# Supply_HV_ISOL.net
KiCad netlist of a schematic drawn in Altium Designer
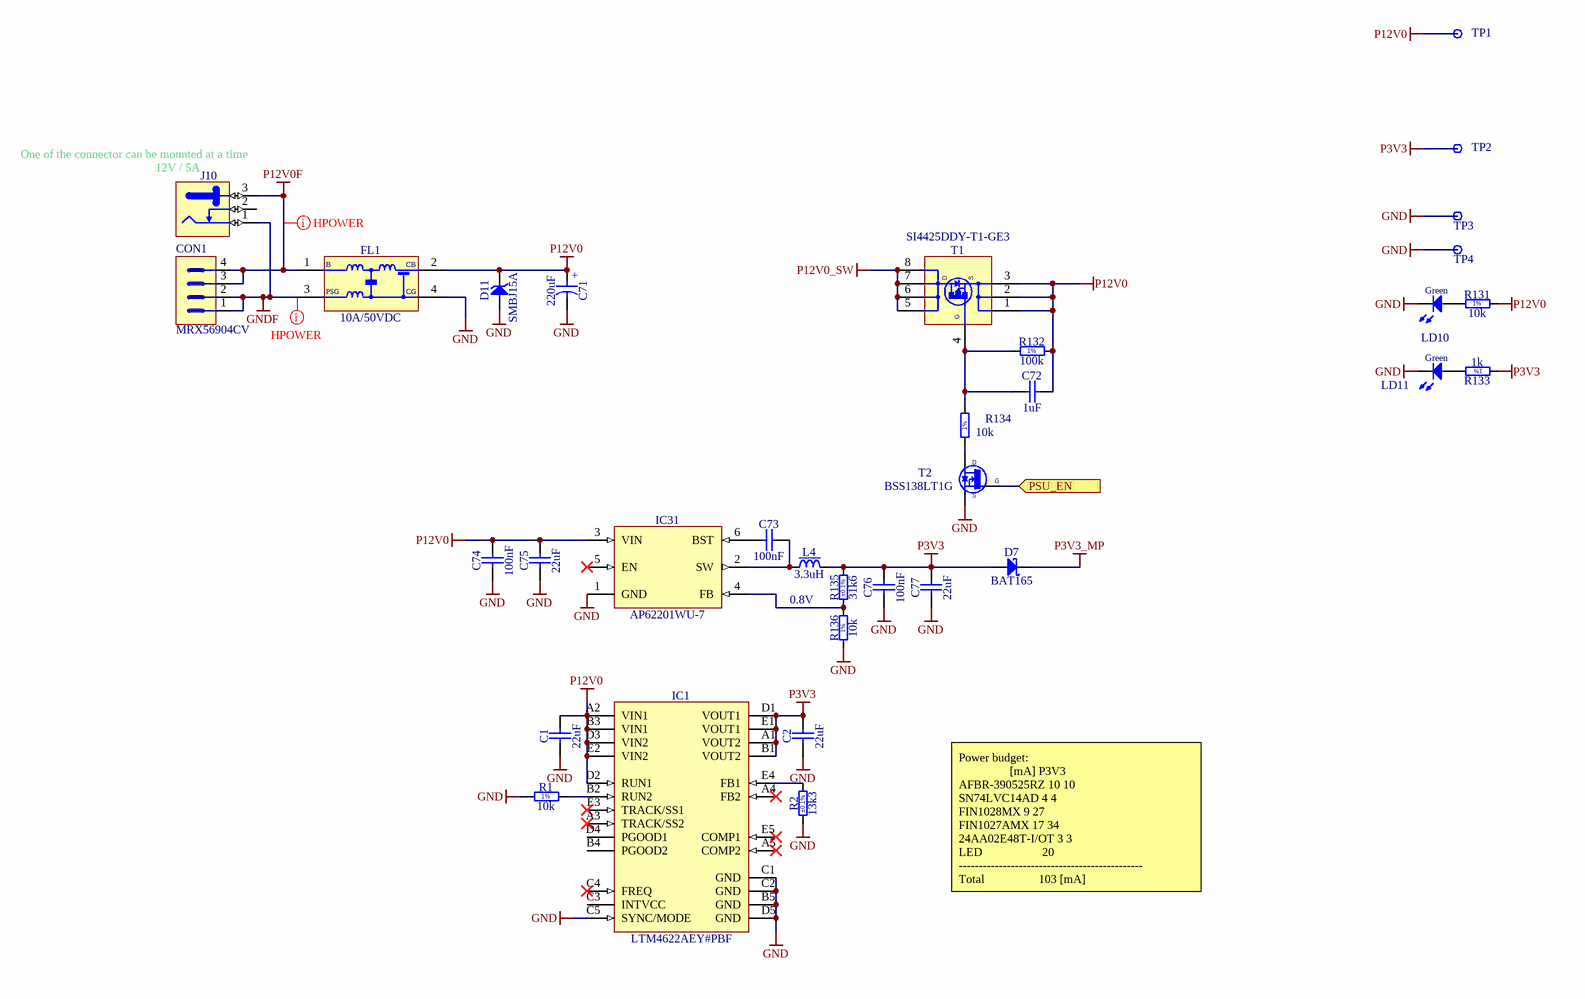
[diagram p0: Supply_HV_ISOL.SchDoc]

(export (version "E")
  (design (tool "Eeschema 10.0.6"))
  (components
    (comp (ref "C1")
      (value "22uF")
      (footprint "CAPC2012X135N")
      (description "Non-polarised capacitor")
      (fields
        (field (name "PART NUMBER") "CC0805_22UF_16V_10%_X5R")
        (field (name "VOLTAGE") "16V")
        (field (name "AUTHOR") "CERN DEM JLC")
      )
      (libsource (lib "Capacitors") (part "Capacitor - non polarized"))
    )
    (comp (ref "C2")
      (value "22uF")
      (footprint "CAPC2012X135N")
      (description "Non-polarised capacitor")
      (fields
        (field (name "PART NUMBER") "CC0805_22UF_16V_10%_X5R")
        (field (name "VOLTAGE") "16V")
        (field (name "AUTHOR") "CERN DEM JLC")
      )
      (libsource (lib "Capacitors") (part "Capacitor - non polarized"))
    )
    (comp (ref "C71")
      (value "220uF")
      (footprint "CAPAE830X620N")
      (description "Polarised capacitor")
      (fields
        (field (name "PART NUMBER") "CAE830-620_220UF_16V_20%")
        (field (name "VOLTAGE") "16V")
        (field (name "AUTHOR") "CERN DEM JLC")
      )
      (libsource (lib "Capacitors") (part "Capacitor - polarized"))
    )
    (comp (ref "C72")
      (value "1uF")
      (footprint "CAPC1005X55N")
      (description "Non-polarised capacitor")
      (fields
        (field (name "PART NUMBER") "CC0402_1UF_16V_10%_X5R")
        (field (name "VOLTAGE") "16V")
        (field (name "AUTHOR") "CERN DEM JLC")
      )
      (libsource (lib "Capacitors") (part "Capacitor - non polarized"))
    )
    (comp (ref "C73")
      (value "100nF")
      (footprint "CAPC1005X55N")
      (description "Non-polarised capacitor")
      (fields
        (field (name "PART NUMBER") "CC0402_100NF_16V_10%_X5R")
        (field (name "VOLTAGE") "16V")
        (field (name "AUTHOR") "CERN DEM JLC")
      )
      (libsource (lib "Capacitors") (part "Capacitor - non polarized"))
    )
    (comp (ref "C74")
      (value "100nF")
      (footprint "CAPC1005X55N")
      (description "Non-polarised capacitor")
      (fields
        (field (name "PART NUMBER") "CC0402_100NF_16V_10%_X5R")
        (field (name "VOLTAGE") "16V")
        (field (name "AUTHOR") "CERN DEM JLC")
      )
      (libsource (lib "Capacitors") (part "Capacitor - non polarized"))
    )
    (comp (ref "C75")
      (value "22uF")
      (footprint "CAPC2012X135N")
      (description "Non-polarised capacitor")
      (fields
        (field (name "PART NUMBER") "CC0805_22UF_16V_10%_X5R")
        (field (name "VOLTAGE") "16V")
        (field (name "AUTHOR") "CERN DEM JLC")
      )
      (libsource (lib "Capacitors") (part "Capacitor - non polarized"))
    )
    (comp (ref "C76")
      (value "100nF")
      (footprint "CAPC1005X55N")
      (description "Non-polarised capacitor")
      (fields
        (field (name "PART NUMBER") "CC0402_100NF_16V_10%_X5R")
        (field (name "VOLTAGE") "16V")
        (field (name "AUTHOR") "CERN DEM JLC")
      )
      (libsource (lib "Capacitors") (part "Capacitor - non polarized"))
    )
    (comp (ref "C77")
      (value "22uF")
      (footprint "CAPC2012X135N")
      (description "Non-polarised capacitor")
      (fields
        (field (name "PART NUMBER") "CC0805_22UF_16V_10%_X5R")
        (field (name "VOLTAGE") "16V")
        (field (name "AUTHOR") "CERN DEM JLC")
      )
      (libsource (lib "Capacitors") (part "Capacitor - non polarized"))
    )
    (comp (ref "CON1")
      (value "MRX56904CV")
      (footprint "MRX56904CV")
      (description "4.2mm cripm terminal header")
      (libsource (lib "LIBRARY_SCH") (part "CON_CRIMP_4.2mm_RA_4"))
    )
    (comp (ref "D7")
      (value "BAT165")
      (footprint "SOD2512X110N")
      (description "Schottky Diode")
      (fields
        (field (name "VOLTAGE") "40V")
        (field (name "POWER") "750mA")
        (field (name "AUTHOR") "CERN DEM JLC")
      )
      (libsource (lib "ICs And Semiconductors") (part "Diode Schottky"))
    )
    (comp (ref "D11")
      (value "SMBJ15A")
      (footprint "DIOM5336X265N")
      (description "Zener Diode")
      (fields
        (field (name "VOLTAGE") "15V")
        (field (name "POWER") "600W")
        (field (name "AUTHOR") "CERN DEM JLC")
      )
      (libsource (lib "ICs And Semiconductors") (part "Diode Zener"))
    )
    (comp (ref "FL1")
      (value "10A/50VDC")
      (footprint "FIL_MURATA_BNX02")
      (description "Block Type EMIFIL (LC Combined)")
      (fields
        (field (name "PART NUMBER") "FIL_MURATA_BNX022-01L")
        (field (name "MANUFACTURER") "MURATA")
        (field (name "AUTHOR") "CERN DEM JLC")
      )
      (libsource (lib "Inductors & Transformers") (part "FIL_MURATA_BNX02"))
    )
    (comp (ref "IC1")
      (value "LTM4622AEY#PBF")
      (footprint "BGA25C127P5X5_625X625X262")
      (description "3.6V-20V To 1.5V-12V, Dual 2A or Single 4A  Ultrathin Step-Down DC/DC µModule Regulator")
      (fields (field (name "MANUFACTURER") "LINEAR TECHNOLOGY") (field (name "AUTHOR") "CERN DEM MR"))
      (libsource (lib "ICs And Semiconductors") (part "LTM4622A"))
    )
    (comp (ref "IC31")
      (value "AP62201WU-7")
      (footprint "SOT95P280X100-6N")
      (description "4.2V TO 18V INPUT, 2A LOW IQ SYNCHRONOUS BUCK CONVERTER")
      (fields (field (name "MANUFACTURER") "DIODES INCORPORATED") (field (name "AUTHOR") "CERN DEM HF"))
      (libsource (lib "ICs And Semiconductors") (part "AP62201WU"))
    )
    (comp (ref "J10")
      (value "Jack")
      (footprint "SWITCHCRAFT_L712RA")
      (description "24V /3. 5A, 2.1mm Diameter Pin, SMD DC Power Supply Connector With  Break Contact")
      (fields
        (field (name "PART NUMBER") "SWITCHCRAFT_L712RA")
        (field (name "MANUFACTURER") "SWITCHCRAFT")
        (field (name "AUTHOR") "GK")
      )
      (libsource (lib "LIBRARY_SCH") (part "CON_DC_5A_THT_RA"))
    )
    (comp (ref "L4")
      (value "3.3uH")
      (footprint "IND_WURTH_WE-TPC_4828")
      (description "Inductor With Core")
      (fields
        (field (name "PART NUMBER") "IND_3.3UH_30%_WURTH_WE-TPC_744043003")
        (field (name "POWER") "2.15A")
        (field (name "AUTHOR") "CERN DEM JLC")
      )
      (libsource (lib "Inductors & Transformers") (part "Inductor With Magnetic core"))
    )
    (comp (ref "LD10")
      (value "Green")
      (footprint "LED_KINGBRIGHT_KPH-1608CGCK")
      (description "LED Green 1C 2A")
      (fields
        (field (name "PART NUMBER") "LED_KINGBRIGHT_KPH-1608CGCK")
        (field (name "MANUFACTURER") "KINGBRIGHT")
        (field (name "AUTHOR") "CERN DEM JLC")
      )
      (libsource (lib "ICs And Semiconductors") (part "LED Green 1C 2A"))
    )
    (comp (ref "LD11")
      (value "Green")
      (footprint "LED_KINGBRIGHT_KPH-1608CGCK")
      (description "LED Green 1C 2A")
      (fields
        (field (name "PART NUMBER") "LED_KINGBRIGHT_KPH-1608CGCK")
        (field (name "MANUFACTURER") "KINGBRIGHT")
        (field (name "AUTHOR") "CERN DEM JLC")
      )
      (libsource (lib "ICs And Semiconductors") (part "LED Green 1C 2A"))
    )
    (comp (ref "R1")
      (value "10k")
      (footprint "RESC1005X40N")
      (description "Resistor - 1%")
      (fields
        (field (name "PART NUMBER") "R0402_10K_1%_0.0625W_100PPM")
        (field (name "POWER") "0.0625W")
        (field (name "AUTHOR") "CERN DEM JLC")
      )
      (libsource (lib "Resistors") (part "Resistor - 1%"))
    )
    (comp (ref "R2")
      (value "13k3")
      (footprint "RESC1608X55N")
      (description "Resistor - 0.1%")
      (fields
        (field (name "TOLERANCE") "±0.1%")
        (field (name "PART NUMBER") "R0603_13K3_0.1%_0.063W_10PPM")
        (field (name "POWER") "0.063W")
        (field (name "AUTHOR") "CERN DEM JLC")
      )
      (libsource (lib "Resistors") (part "Resistor - 0.1%"))
    )
    (comp (ref "R131")
      (value "10k")
      (footprint "RESC1005X40N")
      (description "Resistor - 1%")
      (fields
        (field (name "PART NUMBER") "R0402_10K_1%_0.0625W_100PPM")
        (field (name "POWER") "0.0625W")
        (field (name "AUTHOR") "CERN DEM JLC")
      )
      (libsource (lib "Resistors") (part "Resistor - 1%"))
    )
    (comp (ref "R132")
      (value "100k")
      (footprint "RESC1608X55N")
      (description "Resistor - 1%")
      (fields
        (field (name "PART NUMBER") "R0603_100K_1%_0.1W_100PPM")
        (field (name "POWER") "0.1W")
        (field (name "AUTHOR") "CERN DEM JLC")
      )
      (libsource (lib "Resistors") (part "Resistor - 1%"))
    )
    (comp (ref "R133")
      (value "1k")
      (footprint "RESC1608X55N")
      (description "Resistor - 1%")
      (fields
        (field (name "PART NUMBER") "R0603_1K_1%_0.1W_100PPM")
        (field (name "POWER") "0.1W")
        (field (name "AUTHOR") "CERN DEM JLC")
      )
      (libsource (lib "Resistors") (part "Resistor - 1%"))
    )
    (comp (ref "R134")
      (value "10k")
      (footprint "RESC1005X40N")
      (description "Resistor - 1%")
      (fields
        (field (name "PART NUMBER") "R0402_10K_1%_0.0625W_100PPM")
        (field (name "POWER") "0.0625W")
        (field (name "AUTHOR") "CERN DEM JLC")
      )
      (libsource (lib "Resistors") (part "Resistor - 1%"))
    )
    (comp (ref "R135")
      (value "31k6")
      (footprint "RESC1005X35N")
      (description "Resistor - 0.1%")
      (fields
        (field (name "TOLERANCE") "±0.1%")
        (field (name "PART NUMBER") "R0402_31K6_0.1%_0.063W_25PPM_YAGEO_RT")
        (field (name "POWER") "0.063W")
        (field (name "AUTHOR") "CERN DEM BC")
      )
      (libsource (lib "Resistors") (part "Resistor - 0.1%"))
    )
    (comp (ref "R136")
      (value "10k")
      (footprint "RESC1005X40N")
      (description "Resistor - 1%")
      (fields
        (field (name "PART NUMBER") "R0402_10K_1%_0.0625W_100PPM")
        (field (name "POWER") "0.0625W")
        (field (name "AUTHOR") "CERN DEM JLC")
      )
      (libsource (lib "Resistors") (part "Resistor - 1%"))
    )
    (comp (ref "T1")
      (value "SI4425DDY-T1-GE3")
      (footprint "SOIC127P600X175-8N")
      (description "-30V -19.7A P-Channel MOSFET")
      (fields (field (name "MANUFACTURER") "VISHAY SILICONIX") (field (name "AUTHOR") "CERN DEM MR"))
      (libsource (lib "ICs And Semiconductors") (part "SI4425DDY"))
    )
    (comp (ref "T2")
      (value "BSS138LT1G")
      (footprint "SOT95P240X110-3N")
      (description "N-CHANNEL MOSFET WITH DIODE")
      (fields (field (name "MANUFACTURER") "ON SEMICONDUCTOR") (field (name "AUTHOR") "CERN DEM JLC"))
      (libsource (lib "ICs And Semiconductors") (part "N-MOSFET-D 1G 2S 3D"))
    )
    (comp (ref "TP1")
      (value "Test Point")
      (footprint "TPS127")
      (fields (field (name "PART NUMBER") "SMD_PAD_1.27X1.27MM") (field (name "AUTHOR") "CERN DEM JLC"))
      (libsource (lib "Eletro-mechanical") (part "Test Point"))
    )
    (comp (ref "TP2")
      (value "Test Point")
      (footprint "TPS127")
      (fields (field (name "PART NUMBER") "SMD_PAD_1.27X1.27MM") (field (name "AUTHOR") "CERN DEM JLC"))
      (libsource (lib "Eletro-mechanical") (part "Test Point"))
    )
    (comp (ref "TP3")
      (value "Test Point")
      (footprint "TPS127")
      (fields (field (name "PART NUMBER") "SMD_PAD_1.27X1.27MM") (field (name "AUTHOR") "CERN DEM JLC"))
      (libsource (lib "Eletro-mechanical") (part "Test Point"))
    )
    (comp (ref "TP4")
      (value "Test Point")
      (footprint "TPS127")
      (fields (field (name "PART NUMBER") "SMD_PAD_1.27X1.27MM") (field (name "AUTHOR") "CERN DEM JLC"))
      (libsource (lib "Eletro-mechanical") (part "Test Point"))
    )
  )
  (nets
    (net (code "1") (name "/PSU_EN") (class "Default")
      (node (ref "T2") (pin "1") (pinfunction "G_1") (pintype "passive"))
    )
    (net (code "2") (name "GND") (class "Default")
      (node (ref "C1") (pin "1") (pinfunction "1_1") (pintype "passive"))
      (node (ref "C2") (pin "1") (pinfunction "1_1") (pintype "passive"))
      (node (ref "C71") (pin "2") (pinfunction "2_2") (pintype "passive"))
      (node (ref "C74") (pin "1") (pinfunction "1_1") (pintype "passive"))
      (node (ref "C75") (pin "1") (pinfunction "1_1") (pintype "passive"))
      (node (ref "C76") (pin "1") (pinfunction "1_1") (pintype "passive"))
      (node (ref "C77") (pin "1") (pinfunction "1_1") (pintype "passive"))
      (node (ref "D11") (pin "2") (pinfunction "A_2") (pintype "passive"))
      (node (ref "FL1") (pin "4") (pinfunction "CG_4") (pintype "passive"))
      (node (ref "IC1") (pin "B5") (pinfunction "GND_B5") (pintype "power_in"))
      (node (ref "IC1") (pin "C1") (pinfunction "GND_C1") (pintype "power_in"))
      (node (ref "IC1") (pin "C2") (pinfunction "GND_C2") (pintype "power_in"))
      (node (ref "IC1") (pin "C5") (pinfunction "SYNC/MODE_C5") (pintype "input"))
      (node (ref "IC1") (pin "D5") (pinfunction "GND_D5") (pintype "power_in"))
      (node (ref "IC31") (pin "1") (pinfunction "GND_1") (pintype "power_in"))
      (node (ref "LD10") (pin "1") (pinfunction "C_1") (pintype "passive"))
      (node (ref "LD11") (pin "1") (pinfunction "C_1") (pintype "passive"))
      (node (ref "R1") (pin "1") (pinfunction "1_1") (pintype "passive"))
      (node (ref "R136") (pin "1") (pinfunction "1_1") (pintype "passive"))
      (node (ref "R2") (pin "1") (pinfunction "1_1") (pintype "passive"))
      (node (ref "T2") (pin "2") (pinfunction "S_2") (pintype "passive"))
      (node (ref "TP3") (pin "1") (pinfunction "1_1") (pintype "bidirectional"))
      (node (ref "TP4") (pin "1") (pinfunction "1_1") (pintype "bidirectional"))
    )
    (net (code "3") (name "GNDF") (class "Default")
      (node (ref "CON1") (pin "1") (pinfunction "1_1") (pintype "bidirectional"))
      (node (ref "CON1") (pin "2") (pinfunction "2_2") (pintype "bidirectional"))
      (node (ref "FL1") (pin "3") (pinfunction "PSG_3") (pintype "passive"))
      (node (ref "J10") (pin "1") (pinfunction "1_1") (pintype "bidirectional"))
    )
    (net (code "4") (name "Net-(C72-Pad1)") (class "Default")
      (node (ref "C72") (pin "1") (pinfunction "1_1") (pintype "passive"))
      (node (ref "R132") (pin "1") (pinfunction "1_1") (pintype "passive"))
      (node (ref "R134") (pin "2") (pinfunction "2_2") (pintype "passive"))
      (node (ref "T1") (pin "4") (pinfunction "S_4") (pintype "passive"))
    )
    (net (code "5") (name "Net-(IC1-FB1)") (class "Default")
      (node (ref "IC1") (pin "E4") (pinfunction "FB1_E4") (pintype "input"))
      (node (ref "R2") (pin "2") (pinfunction "2_2") (pintype "passive"))
    )
    (net (code "6") (name "Net-(IC1-RUN2)") (class "Default")
      (node (ref "IC1") (pin "B2") (pinfunction "RUN2_B2") (pintype "input"))
      (node (ref "R1") (pin "2") (pinfunction "2_2") (pintype "passive"))
    )
    (net (code "7") (name "Net-(IC31-BST)") (class "Default")
      (node (ref "C73") (pin "1") (pinfunction "1_1") (pintype "passive"))
      (node (ref "IC31") (pin "6") (pinfunction "BST_6") (pintype "input"))
    )
    (net (code "8") (name "Net-(IC31-FB)") (class "Default")
      (node (ref "IC31") (pin "4") (pinfunction "FB_4") (pintype "input"))
      (node (ref "R135") (pin "1") (pinfunction "1_1") (pintype "passive"))
      (node (ref "R136") (pin "2") (pinfunction "2_2") (pintype "passive"))
    )
    (net (code "9") (name "Net-(IC31-SW)") (class "Default")
      (node (ref "C73") (pin "2") (pinfunction "2_2") (pintype "passive"))
      (node (ref "IC31") (pin "2") (pinfunction "SW_2") (pintype "output"))
      (node (ref "L4") (pin "1") (pinfunction "1_1") (pintype "passive"))
    )
    (net (code "10") (name "Net-(LD10-A)") (class "Default")
      (node (ref "LD10") (pin "2") (pinfunction "A_2") (pintype "passive"))
      (node (ref "R131") (pin "1") (pinfunction "1_1") (pintype "passive"))
    )
    (net (code "11") (name "Net-(LD11-A)") (class "Default")
      (node (ref "LD11") (pin "2") (pinfunction "A_2") (pintype "passive"))
      (node (ref "R133") (pin "2") (pinfunction "2_2") (pintype "passive"))
    )
    (net (code "12") (name "Net-(T2-D)") (class "Default")
      (node (ref "R134") (pin "1") (pinfunction "1_1") (pintype "passive"))
      (node (ref "T2") (pin "3") (pinfunction "D_3") (pintype "passive"))
    )
    (net (code "13") (name "P3V3") (class "Default")
      (node (ref "C2") (pin "2") (pinfunction "2_2") (pintype "passive"))
      (node (ref "C76") (pin "2") (pinfunction "2_2") (pintype "passive"))
      (node (ref "C77") (pin "2") (pinfunction "2_2") (pintype "passive"))
      (node (ref "D7") (pin "2") (pinfunction "A_2") (pintype "passive"))
      (node (ref "IC1") (pin "A1") (pinfunction "VOUT2_A1") (pintype "power_in"))
      (node (ref "IC1") (pin "B1") (pinfunction "VOUT2_B1") (pintype "power_in"))
      (node (ref "IC1") (pin "D1") (pinfunction "VOUT1_D1") (pintype "power_in"))
      (node (ref "IC1") (pin "E1") (pinfunction "VOUT1_E1") (pintype "power_in"))
      (node (ref "L4") (pin "2") (pinfunction "2_2") (pintype "passive"))
      (node (ref "R133") (pin "1") (pinfunction "1_1") (pintype "passive"))
      (node (ref "R135") (pin "2") (pinfunction "2_2") (pintype "passive"))
      (node (ref "TP2") (pin "1") (pinfunction "1_1") (pintype "bidirectional"))
    )
    (net (code "14") (name "P3V3_MP") (class "Default")
      (node (ref "D7") (pin "1") (pinfunction "C_1") (pintype "passive"))
    )
    (net (code "15") (name "P12V0") (class "Default")
      (node (ref "C1") (pin "2") (pinfunction "2_2") (pintype "passive"))
      (node (ref "C71") (pin "1") (pinfunction "1_1") (pintype "passive"))
      (node (ref "C72") (pin "2") (pinfunction "2_2") (pintype "passive"))
      (node (ref "C74") (pin "2") (pinfunction "2_2") (pintype "passive"))
      (node (ref "C75") (pin "2") (pinfunction "2_2") (pintype "passive"))
      (node (ref "D11") (pin "1") (pinfunction "C_1") (pintype "passive"))
      (node (ref "FL1") (pin "2") (pinfunction "CB_2") (pintype "passive"))
      (node (ref "IC1") (pin "A2") (pinfunction "VIN1_A2") (pintype "power_in"))
      (node (ref "IC1") (pin "B3") (pinfunction "VIN1_B3") (pintype "power_in"))
      (node (ref "IC1") (pin "D2") (pinfunction "RUN1_D2") (pintype "input"))
      (node (ref "IC1") (pin "D3") (pinfunction "VIN2_D3") (pintype "power_in"))
      (node (ref "IC1") (pin "E2") (pinfunction "VIN2_E2") (pintype "power_in"))
      (node (ref "IC31") (pin "3") (pinfunction "VIN_3") (pintype "input"))
      (node (ref "R131") (pin "2") (pinfunction "2_2") (pintype "passive"))
      (node (ref "R132") (pin "2") (pinfunction "2_2") (pintype "passive"))
      (node (ref "T1") (pin "1") (pinfunction "S_1") (pintype "passive"))
      (node (ref "T1") (pin "2") (pinfunction "S_2") (pintype "passive"))
      (node (ref "T1") (pin "3") (pinfunction "S_3") (pintype "passive"))
      (node (ref "TP1") (pin "1") (pinfunction "1_1") (pintype "bidirectional"))
    )
    (net (code "16") (name "P12V0F") (class "Default")
      (node (ref "CON1") (pin "3") (pinfunction "3_3") (pintype "bidirectional"))
      (node (ref "CON1") (pin "4") (pinfunction "4_4") (pintype "bidirectional"))
      (node (ref "FL1") (pin "1") (pinfunction "B_1") (pintype "passive"))
      (node (ref "J10") (pin "3") (pinfunction "3_3") (pintype "bidirectional"))
    )
    (net (code "17") (name "P12V0_SW") (class "Default")
      (node (ref "T1") (pin "5") (pinfunction "D_5") (pintype "passive"))
      (node (ref "T1") (pin "6") (pinfunction "D_6") (pintype "passive"))
      (node (ref "T1") (pin "7") (pinfunction "D_7") (pintype "passive"))
      (node (ref "T1") (pin "8") (pinfunction "D_8") (pintype "passive"))
    )
    (net (code "18") (name "unconnected-(IC1-COMP1-PadE5)") (class "Default")
      (node (ref "IC1") (pin "E5") (pinfunction "COMP1_E5") (pintype "input+no_connect"))
    )
    (net (code "19") (name "unconnected-(IC1-COMP2-PadA5)") (class "Default")
      (node (ref "IC1") (pin "A5") (pinfunction "COMP2_A5") (pintype "input+no_connect"))
    )
    (net (code "20") (name "unconnected-(IC1-FB2-PadA4)") (class "Default")
      (node (ref "IC1") (pin "A4") (pinfunction "FB2_A4") (pintype "input+no_connect"))
    )
    (net (code "21") (name "unconnected-(IC1-FREQ-PadC4)") (class "Default")
      (node (ref "IC1") (pin "C4") (pinfunction "FREQ_C4") (pintype "input+no_connect"))
    )
    (net (code "22") (name "unconnected-(IC1-INTVCC-PadC3)") (class "Default")
      (node (ref "IC1") (pin "C3") (pinfunction "INTVCC_C3") (pintype "power_in"))
    )
    (net (code "23") (name "unconnected-(IC1-PGOOD1-PadD4)") (class "Default")
      (node (ref "IC1") (pin "D4") (pinfunction "PGOOD1_D4") (pintype "open_collector"))
    )
    (net (code "24") (name "unconnected-(IC1-PGOOD2-PadB4)") (class "Default")
      (node (ref "IC1") (pin "B4") (pinfunction "PGOOD2_B4") (pintype "open_collector"))
    )
    (net (code "25") (name "unconnected-(IC1-TRACK{slash}SS1-PadE3)") (class "Default")
      (node (ref "IC1") (pin "E3") (pinfunction "TRACK/SS1_E3") (pintype "input+no_connect"))
    )
    (net (code "26") (name "unconnected-(IC1-TRACK{slash}SS2-PadA3)") (class "Default")
      (node (ref "IC1") (pin "A3") (pinfunction "TRACK/SS2_A3") (pintype "input+no_connect"))
    )
    (net (code "27") (name "unconnected-(IC31-EN-Pad5)") (class "Default")
      (node (ref "IC31") (pin "5") (pinfunction "EN_5") (pintype "input+no_connect"))
    )
    (net (code "28") (name "unconnected-(J10-Pad2)") (class "Default")
      (node (ref "J10") (pin "2") (pinfunction "2_2") (pintype "bidirectional"))
    )
  )
)
